# webench_design_1160921_72_ad14_sim.net
KiCad netlist of a schematic drawn in Altium Designer
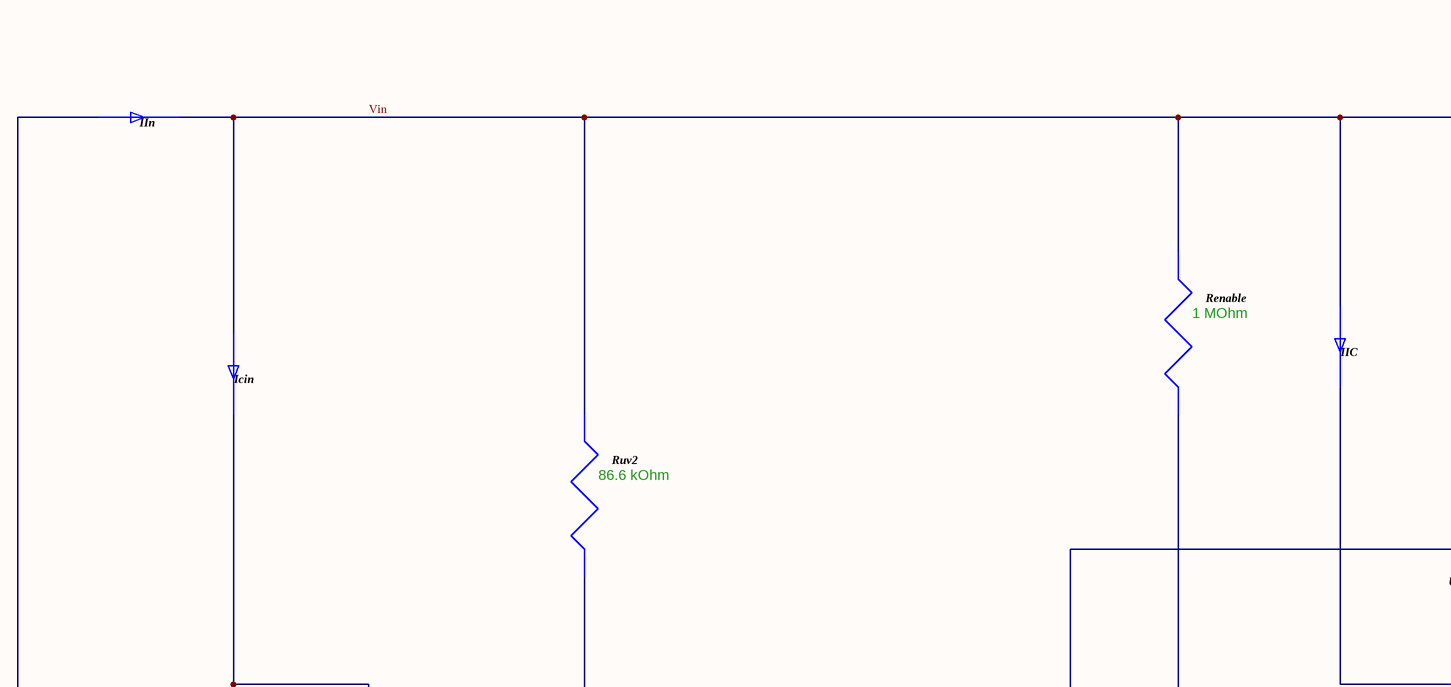
[diagram p0: webench_design_1160921_72_ad14_sim.SchDoc, top left]
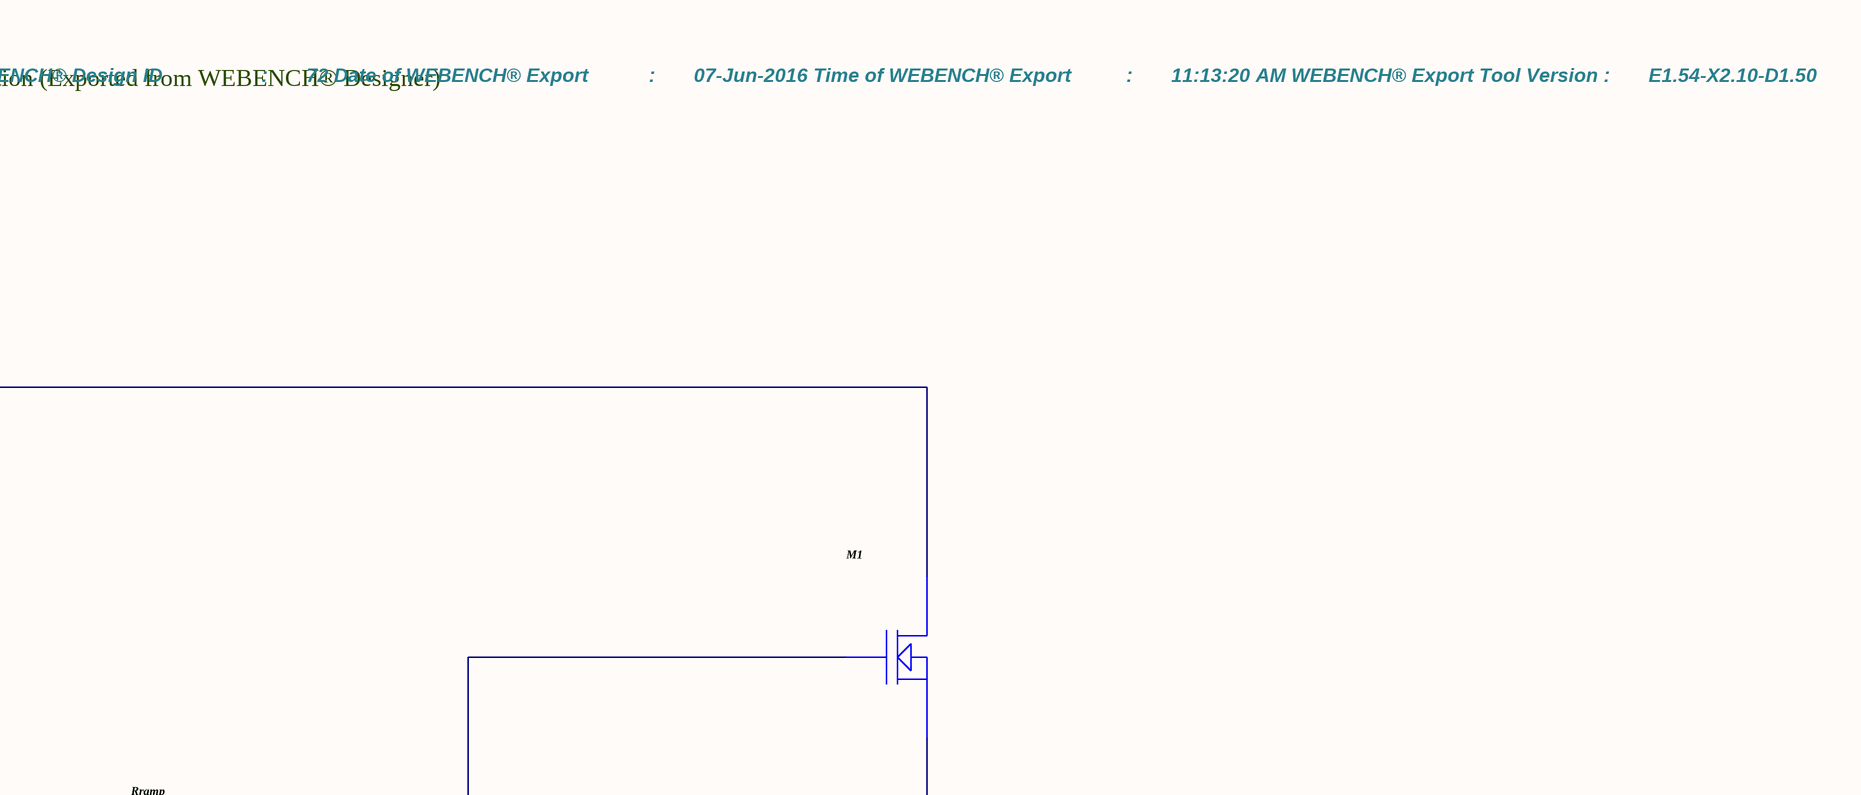
[diagram p1: webench_design_1160921_72_ad14_sim.SchDoc, top right]
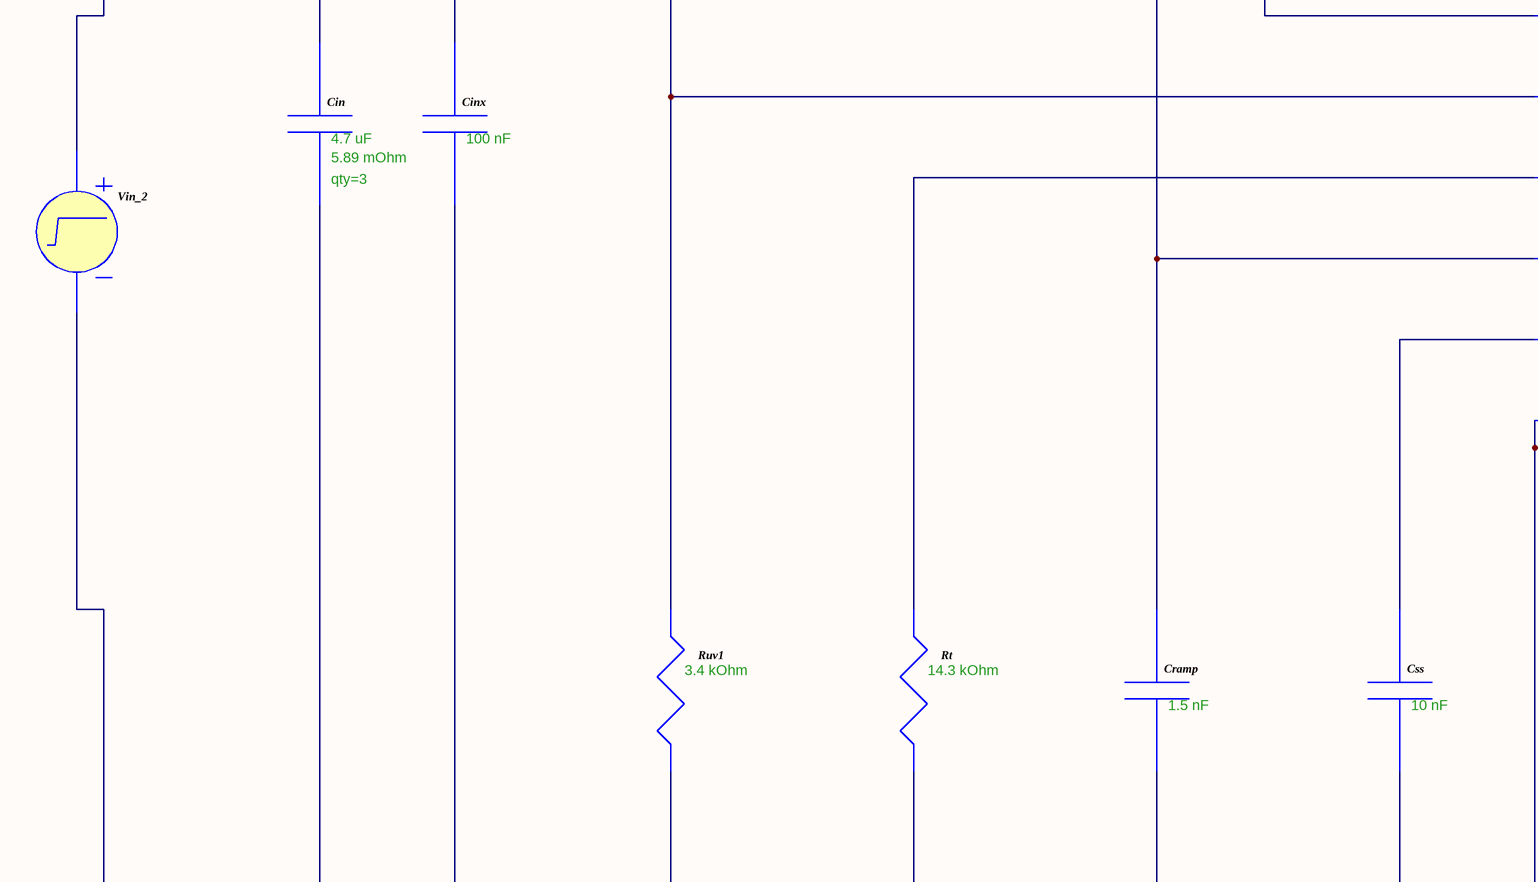
[diagram p2: webench_design_1160921_72_ad14_sim.SchDoc, bottom left]
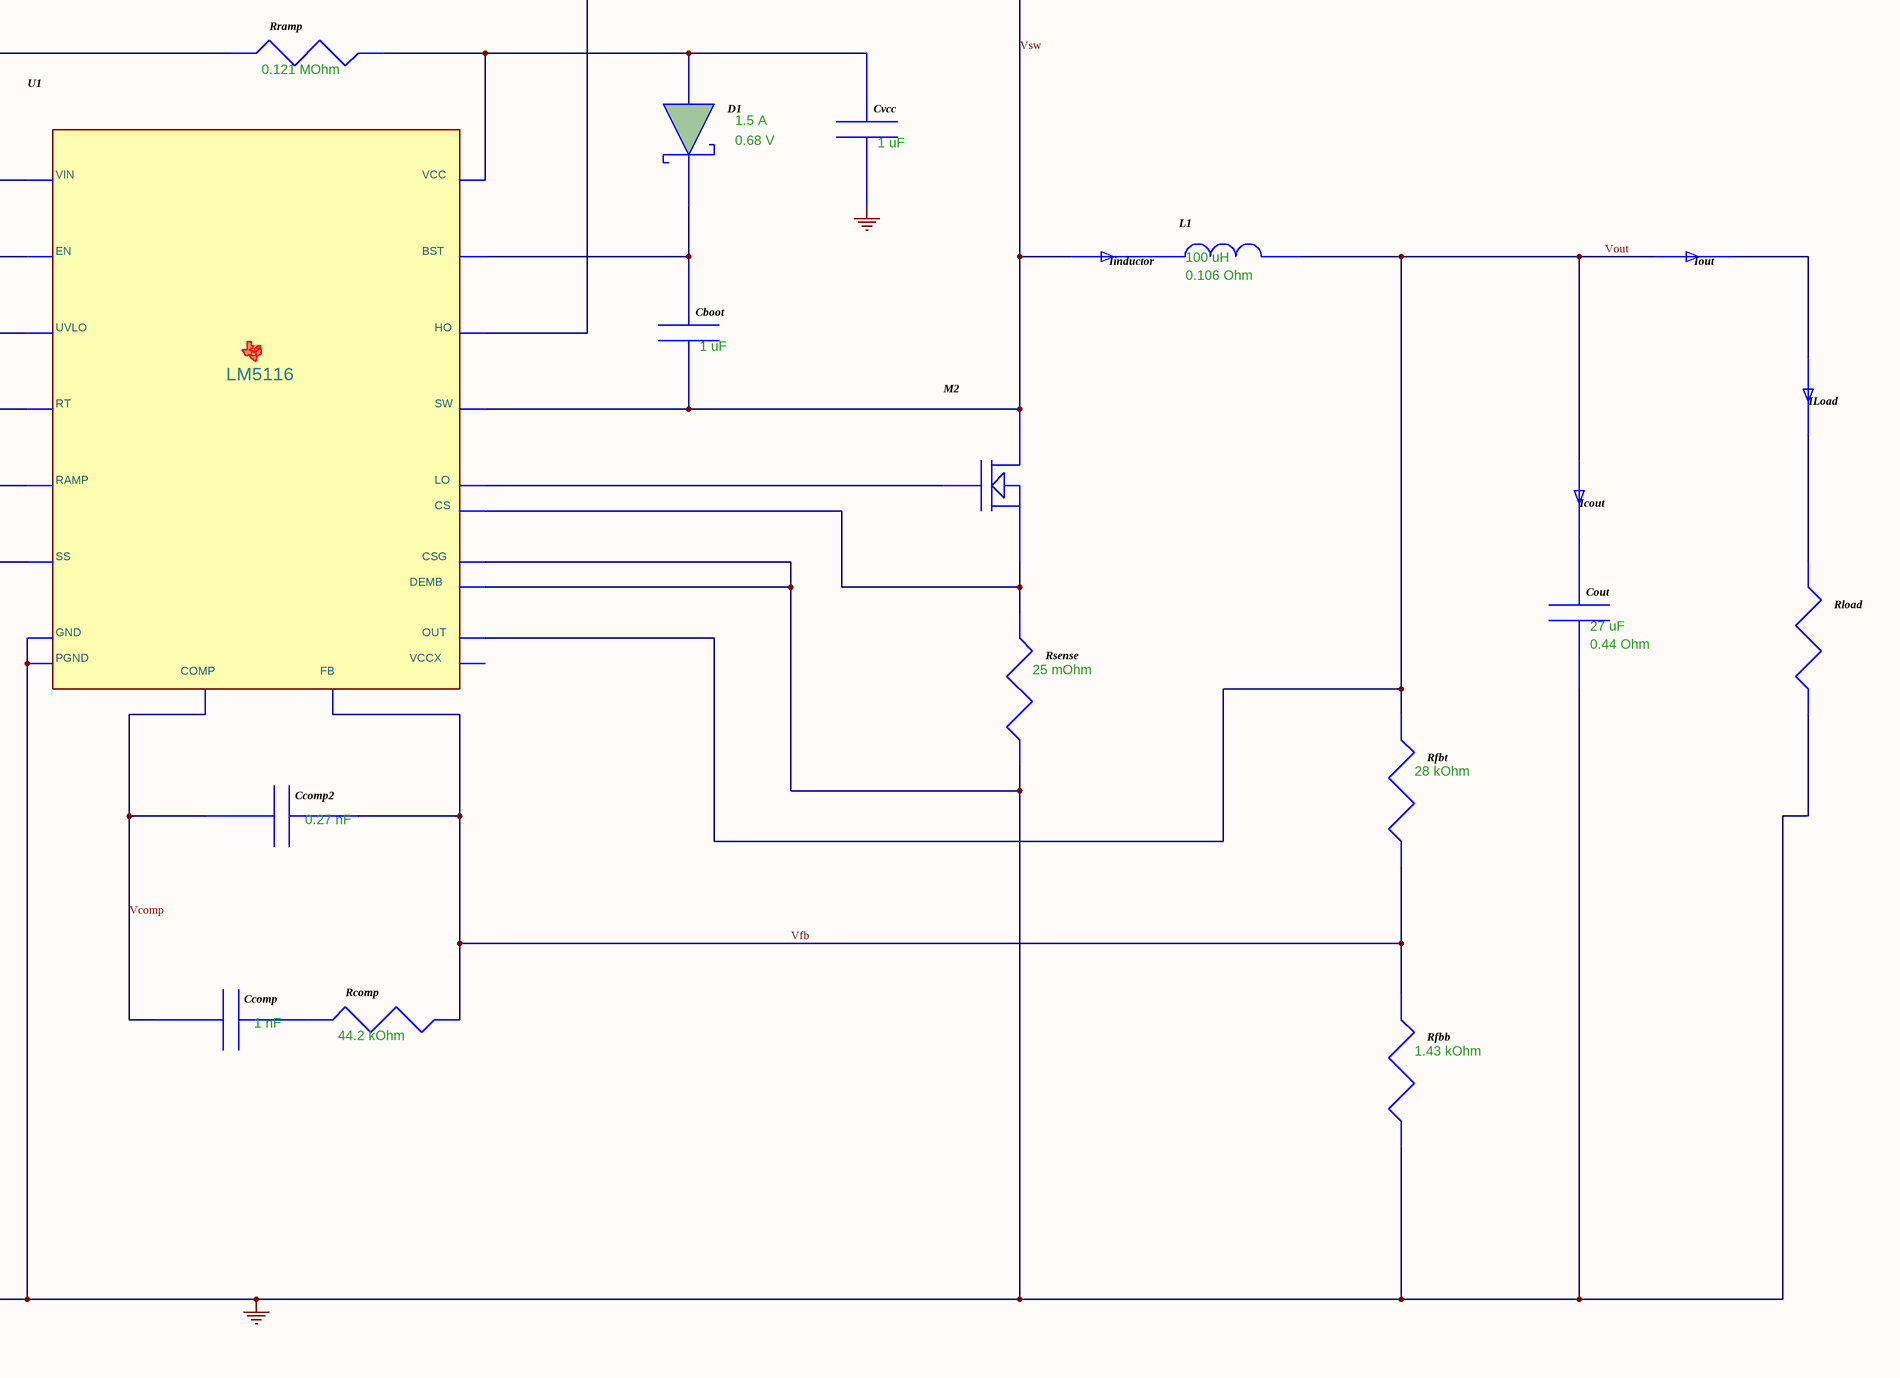
[diagram p3: webench_design_1160921_72_ad14_sim.SchDoc, bottom right]

(export (version "E")
  (design (tool "Eeschema 10.0.6"))
  (components
    (comp (ref "Cboot") (value "~") (libsource (lib "*") (part "Cboot")))
    (comp (ref "Ccomp") (value "~") (libsource (lib "*") (part "Ccomp")))
    (comp (ref "Ccomp2") (value "~") (libsource (lib "*") (part "Ccomp2")))
    (comp (ref "Cin") (value "~") (libsource (lib "*") (part "Cin")))
    (comp (ref "Cinx") (value "~") (libsource (lib "*") (part "Cinx")))
    (comp (ref "Cout") (value "~") (libsource (lib "*") (part "Cout")))
    (comp (ref "Cramp") (value "~") (libsource (lib "*") (part "Cramp")))
    (comp (ref "Css") (value "~") (libsource (lib "*") (part "Css")))
    (comp (ref "Cvcc") (value "~") (libsource (lib "*") (part "Cvcc")))
    (comp (ref "D1") (value "~") (libsource (lib "*") (part "D1")))
    (comp (ref "Icin")
      (value "~")
      (fields
        (field (name "PARAMETER0") "***********************************\n*     Created by WB Importer      *\n***********************************\n.SUBCKT Icin 1 2 \nV_Iprobe 1 2 0.0\n.ENDS")
      )
      (libsource (lib "*") (part "Icin"))
    )
    (comp (ref "Icout")
      (value "~")
      (fields
        (field (name "PARAMETER0") "***********************************\n*     Created by WB Importer      *\n***********************************\n.SUBCKT Icout 1 2 \nV_Iprobe 1 2 0.0\n.ENDS")
      )
      (libsource (lib "*") (part "Icout"))
    )
    (comp (ref "IIC")
      (value "~")
      (fields
        (field (name "PARAMETER0") "***********************************\n*     Created by WB Importer      *\n***********************************\n.SUBCKT IIC 1 2 \nV_Iprobe 1 2 0.0\n.ENDS")
      )
      (libsource (lib "*") (part "IIC"))
    )
    (comp (ref "IIn")
      (value "~")
      (fields
        (field (name "PARAMETER0") "***********************************\n*     Created by WB Importer      *\n***********************************\n.SUBCKT IIn 1 2 \nV_Iprobe 1 2 0.0\n.ENDS")
      )
      (libsource (lib "*") (part "IIn"))
    )
    (comp (ref "Iinductor")
      (value "~")
      (fields
        (field (name "PARAMETER0") "***********************************\n*     Created by WB Importer      *\n***********************************\n.SUBCKT Iinductor 1 2 \nV_Iprobe 1 2 0.0\n.ENDS")
      )
      (libsource (lib "*") (part "Iinductor"))
    )
    (comp (ref "ILoad")
      (value "~")
      (fields
        (field (name "PARAMETER0") "***********************************\n*     Created by WB Importer      *\n***********************************\n.SUBCKT ILoad 1 2 \nV_Iprobe 1 2 0.0\n.ENDS")
      )
      (libsource (lib "*") (part "ILoad"))
    )
    (comp (ref "Iout")
      (value "~")
      (fields
        (field (name "PARAMETER0") "***********************************\n*     Created by WB Importer      *\n***********************************\n.SUBCKT Iout 1 2 \nV_Iprobe 1 2 0.0\n.ENDS")
      )
      (libsource (lib "*") (part "Iout"))
    )
    (comp (ref "L1") (value "~") (libsource (lib "*") (part "L1")))
    (comp (ref "M1") (value "~") (libsource (lib "*") (part "M1")))
    (comp (ref "M2") (value "~") (libsource (lib "*") (part "M2")))
    (comp (ref "Rcomp") (value "~") (libsource (lib "*") (part "Rcomp")))
    (comp (ref "Renable") (value "~") (libsource (lib "*") (part "Renable")))
    (comp (ref "Rfbb") (value "~") (libsource (lib "*") (part "Rfbb")))
    (comp (ref "Rfbt") (value "~") (libsource (lib "*") (part "Rfbt")))
    (comp (ref "Rload") (value "~") (libsource (lib "*") (part "Rload")))
    (comp (ref "Rramp") (value "~") (libsource (lib "*") (part "Rramp")))
    (comp (ref "Rsense") (value "~") (libsource (lib "*") (part "Rsense")))
    (comp (ref "Rt") (value "~") (libsource (lib "*") (part "Rt")))
    (comp (ref "Ruv1") (value "~") (libsource (lib "*") (part "Ruv1")))
    (comp (ref "Ruv2") (value "~") (libsource (lib "*") (part "Ruv2")))
    (comp (ref "U1") (value "~") (libsource (lib "*") (part "U1")))
    (comp (ref "Vin_2") (value "~") (libsource (lib "*") (part "Vin_2")))
  )
  (nets
    (net (code "1") (name "/Vcomp") (class "Default")
      (node (ref "Ccomp") (pin "8") (pinfunction "8_8") (pintype "passive"))
      (node (ref "Ccomp2") (pin "8") (pinfunction "8_8") (pintype "passive"))
      (node (ref "U1") (pin "COMP") (pinfunction "COMP_COMP") (pintype "passive"))
    )
    (net (code "2") (name "/Vfb") (class "Default")
      (node (ref "Ccomp2") (pin "9") (pinfunction "9_9") (pintype "passive"))
      (node (ref "Rcomp") (pin "9") (pinfunction "9_9") (pintype "passive"))
      (node (ref "Rfbb") (pin "9") (pinfunction "9_9") (pintype "passive"))
      (node (ref "Rfbt") (pin "9") (pinfunction "9_9") (pintype "passive"))
      (node (ref "U1") (pin "FB") (pinfunction "FB_FB") (pintype "passive"))
    )
    (net (code "3") (name "/Vin") (class "Default")
      (node (ref "IIC") (pin "1") (pinfunction "1_1") (pintype "passive"))
      (node (ref "IIn") (pin "2") (pinfunction "2_2") (pintype "passive"))
      (node (ref "Icin") (pin "1") (pinfunction "1_1") (pintype "passive"))
      (node (ref "M1") (pin "drain") (pinfunction "drain_drain") (pintype "passive"))
      (node (ref "Renable") (pin "3") (pinfunction "3_3") (pintype "passive"))
      (node (ref "Ruv2") (pin "3") (pinfunction "3_3") (pintype "passive"))
    )
    (net (code "4") (name "/Vout") (class "Default")
      (node (ref "Icout") (pin "1") (pinfunction "1_1") (pintype "passive"))
      (node (ref "Iout") (pin "1") (pinfunction "1_1") (pintype "passive"))
      (node (ref "L1") (pin "2") (pinfunction "2_2") (pintype "passive"))
      (node (ref "Rfbt") (pin "13") (pinfunction "13_13") (pintype "passive"))
      (node (ref "U1") (pin "OUT") (pinfunction "OUT_OUT") (pintype "passive"))
    )
    (net (code "5") (name "/Vsw") (class "Default")
      (node (ref "Cboot") (pin "14") (pinfunction "14_14") (pintype "passive"))
      (node (ref "Iinductor") (pin "1") (pinfunction "1_1") (pintype "passive"))
      (node (ref "M1") (pin "source") (pinfunction "source_source") (pintype "passive"))
      (node (ref "M2") (pin "d1") (pinfunction "d1_d1") (pintype "passive"))
      (node (ref "U1") (pin "SW") (pinfunction "SW_SW") (pintype "passive"))
    )
    (net (code "6") (name "GND") (class "Default")
      (node (ref "Cin") (pin "2") (pinfunction "2_2") (pintype "passive"))
      (node (ref "Cinx") (pin "0") (pinfunction "0_0") (pintype "passive"))
      (node (ref "Cout") (pin "4") (pinfunction "4_4") (pintype "passive"))
      (node (ref "Cramp") (pin "0") (pinfunction "0_0") (pintype "passive"))
      (node (ref "Css") (pin "0") (pinfunction "0_0") (pintype "passive"))
      (node (ref "Cvcc") (pin "0") (pinfunction "0_0") (pintype "passive"))
      (node (ref "Rfbb") (pin "0") (pinfunction "0_0") (pintype "passive"))
      (node (ref "Rload") (pin "2") (pinfunction "2_2") (pintype "passive"))
      (node (ref "Rsense") (pin "0") (pinfunction "0_0") (pintype "passive"))
      (node (ref "Rt") (pin "0") (pinfunction "0_0") (pintype "passive"))
      (node (ref "Ruv1") (pin "0") (pinfunction "0_0") (pintype "passive"))
      (node (ref "U1") (pin "CSG") (pinfunction "CSG_CSG") (pintype "passive"))
      (node (ref "U1") (pin "DEMB") (pinfunction "DEMB_DEMB") (pintype "passive"))
      (node (ref "U1") (pin "GND") (pinfunction "GND_GND") (pintype "passive"))
      (node (ref "U1") (pin "PGND") (pinfunction "PGND_PGND") (pintype "passive"))
      (node (ref "Vin_2") (pin "2") (pinfunction "2_2") (pintype "passive"))
    )
    (net (code "7") (name "Net-(Cboot-Pad11)") (class "Default")
      (node (ref "Cboot") (pin "11") (pinfunction "11_11") (pintype "passive"))
      (node (ref "D1") (pin "11") (pinfunction "11_11") (pintype "passive"))
      (node (ref "U1") (pin "BST") (pinfunction "BST_BST") (pintype "passive"))
    )
    (net (code "8") (name "Net-(Ccomp-Pad24)") (class "Default")
      (node (ref "Ccomp") (pin "24") (pinfunction "24_24") (pintype "passive"))
      (node (ref "Rcomp") (pin "24") (pinfunction "24_24") (pintype "passive"))
    )
    (net (code "9") (name "Net-(Cin-Pad1)") (class "Default")
      (node (ref "Cin") (pin "1") (pinfunction "1_1") (pintype "passive"))
      (node (ref "Cinx") (pin "1") (pinfunction "1_1") (pintype "passive"))
      (node (ref "Icin") (pin "2") (pinfunction "2_2") (pintype "passive"))
    )
    (net (code "10") (name "Net-(Cout-Pad2)") (class "Default")
      (node (ref "Cout") (pin "2") (pinfunction "2_2") (pintype "passive"))
      (node (ref "Icout") (pin "2") (pinfunction "2_2") (pintype "passive"))
    )
    (net (code "11") (name "Net-(Cramp-Pad6)") (class "Default")
      (node (ref "Cramp") (pin "6") (pinfunction "6_6") (pintype "passive"))
      (node (ref "Rramp") (pin "6") (pinfunction "6_6") (pintype "passive"))
      (node (ref "U1") (pin "RAMP") (pinfunction "RAMP_RAMP") (pintype "passive"))
    )
    (net (code "12") (name "Net-(Css-Pad7)") (class "Default")
      (node (ref "Css") (pin "7") (pinfunction "7_7") (pintype "passive"))
      (node (ref "U1") (pin "SS") (pinfunction "SS_SS") (pintype "passive"))
    )
    (net (code "13") (name "Net-(Cvcc-Pad10)") (class "Default")
      (node (ref "Cvcc") (pin "10") (pinfunction "10_10") (pintype "passive"))
      (node (ref "D1") (pin "10") (pinfunction "10_10") (pintype "passive"))
      (node (ref "Rramp") (pin "10") (pinfunction "10_10") (pintype "passive"))
      (node (ref "U1") (pin "VCC") (pinfunction "VCC_VCC") (pintype "passive"))
    )
    (net (code "14") (name "Net-(IIC-Pad2)") (class "Default")
      (node (ref "IIC") (pin "2") (pinfunction "2_2") (pintype "passive"))
      (node (ref "U1") (pin "VIN") (pinfunction "VIN_VIN") (pintype "passive"))
    )
    (net (code "15") (name "Net-(IIn-Pad1)") (class "Default")
      (node (ref "IIn") (pin "1") (pinfunction "1_1") (pintype "passive"))
      (node (ref "Vin_2") (pin "1") (pinfunction "1_1") (pintype "passive"))
    )
    (net (code "16") (name "Net-(ILoad-Pad1)") (class "Default")
      (node (ref "ILoad") (pin "1") (pinfunction "1_1") (pintype "passive"))
      (node (ref "Iout") (pin "2") (pinfunction "2_2") (pintype "passive"))
    )
    (net (code "17") (name "Net-(ILoad-Pad2)") (class "Default")
      (node (ref "ILoad") (pin "2") (pinfunction "2_2") (pintype "passive"))
      (node (ref "Rload") (pin "1") (pinfunction "1_1") (pintype "passive"))
    )
    (net (code "18") (name "Net-(Iinductor-Pad2)") (class "Default")
      (node (ref "Iinductor") (pin "2") (pinfunction "2_2") (pintype "passive"))
      (node (ref "L1") (pin "1") (pinfunction "1_1") (pintype "passive"))
    )
    (net (code "19") (name "Net-(M1-Padgate)") (class "Default")
      (node (ref "M1") (pin "gate") (pinfunction "gate_gate") (pintype "passive"))
      (node (ref "U1") (pin "HO") (pinfunction "HO_HO") (pintype "passive"))
    )
    (net (code "20") (name "Net-(M2-Padg1)") (class "Default")
      (node (ref "M2") (pin "g1") (pinfunction "g1_g1") (pintype "passive"))
      (node (ref "U1") (pin "LO") (pinfunction "LO_LO") (pintype "passive"))
    )
    (net (code "21") (name "Net-(M2-Pads1)") (class "Default")
      (node (ref "M2") (pin "s1") (pinfunction "s1_s1") (pintype "passive"))
      (node (ref "Rsense") (pin "12") (pinfunction "12_12") (pintype "passive"))
      (node (ref "U1") (pin "CS") (pinfunction "CS_CS") (pintype "passive"))
    )
    (net (code "22") (name "Net-(Renable-Pad5)") (class "Default")
      (node (ref "Renable") (pin "5") (pinfunction "5_5") (pintype "passive"))
      (node (ref "U1") (pin "EN") (pinfunction "EN_EN") (pintype "passive"))
    )
    (net (code "23") (name "Net-(Rt-Pad4)") (class "Default")
      (node (ref "Rt") (pin "4") (pinfunction "4_4") (pintype "passive"))
      (node (ref "U1") (pin "RT") (pinfunction "RT_RT") (pintype "passive"))
    )
    (net (code "24") (name "Net-(Ruv1-Pad2)") (class "Default")
      (node (ref "Ruv1") (pin "2") (pinfunction "2_2") (pintype "passive"))
      (node (ref "Ruv2") (pin "2") (pinfunction "2_2") (pintype "passive"))
      (node (ref "U1") (pin "UVLO") (pinfunction "UVLO_UVLO") (pintype "passive"))
    )
    (net (code "25") (name "unconnected-(U1-PadVCCX)") (class "Default")
      (node (ref "U1") (pin "VCCX") (pinfunction "VCCX_VCCX") (pintype "passive"))
    )
  )
)
